# Adafruit_AR1100.net
KiCad netlist of a schematic drawn in EAGLE
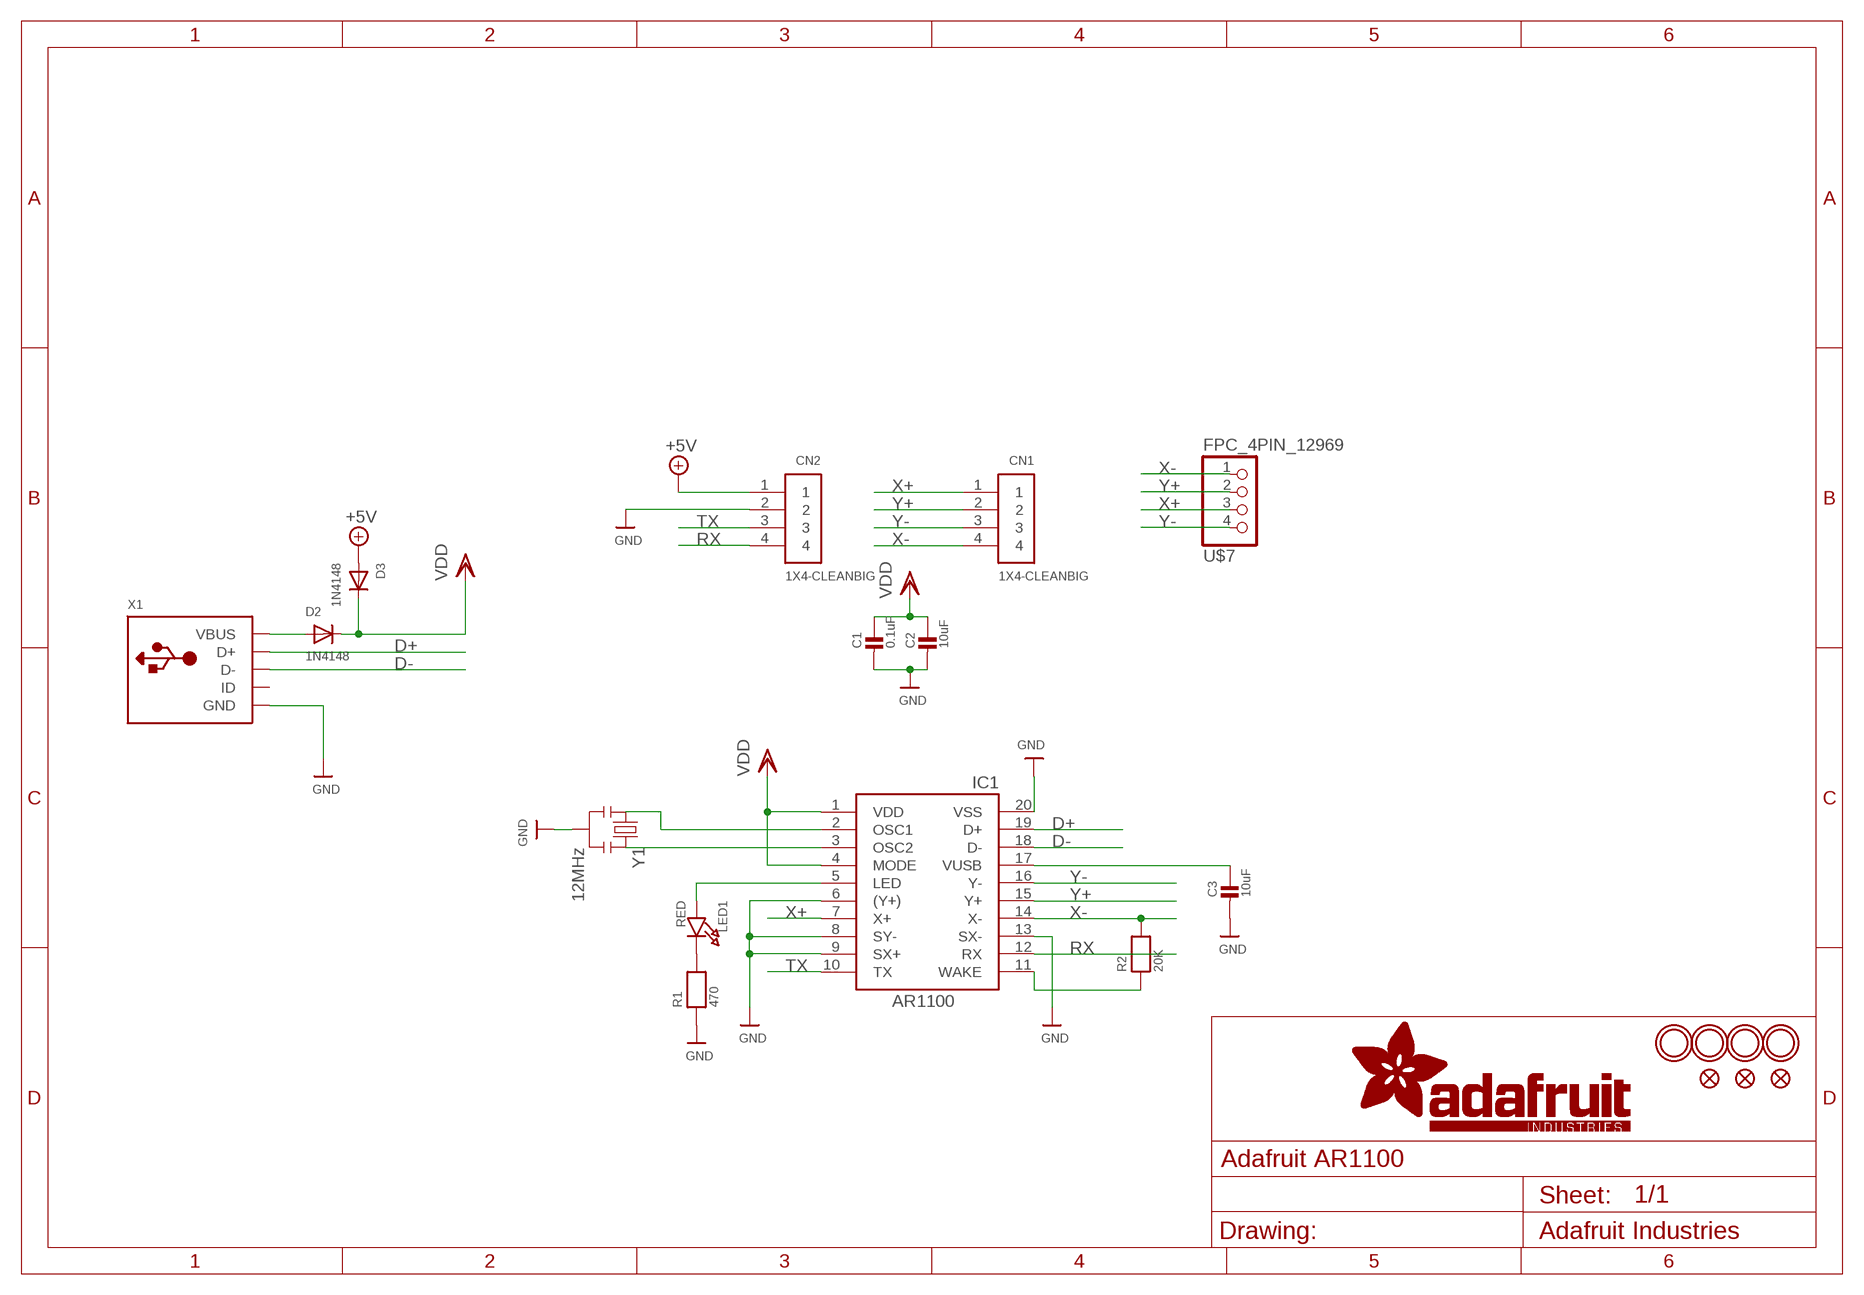
[diagram p0: schematic, sheet 1]

(export (version "E")
  (design (tool "Eeschema 10.0.6"))
  (components
    (comp (ref "C1")
      (value "0.1uF")
      (footprint "eagle-import:0805-NO")
      (libsource (lib "eagle-import") (part "CAP_CERAMIC0805-NOOUTLINE"))
    )
    (comp (ref "C2")
      (value "10uF")
      (footprint "eagle-import:0805-NO")
      (libsource (lib "eagle-import") (part "CAP_CERAMIC0805-NOOUTLINE"))
    )
    (comp (ref "C3")
      (value "10uF")
      (footprint "eagle-import:0805-NO")
      (libsource (lib "eagle-import") (part "CAP_CERAMIC0805-NOOUTLINE"))
    )
    (comp (ref "CN1")
      (value "1X4-CLEANBIG")
      (footprint "eagle-import:1X04-CLEANBIG")
      (libsource (lib "eagle-import") (part "1X4-CLEANBIG"))
    )
    (comp (ref "CN2")
      (value "1X4-CLEANBIG")
      (footprint "eagle-import:1X04-CLEANBIG")
      (libsource (lib "eagle-import") (part "1X4-CLEANBIG"))
    )
    (comp (ref "D2")
      (value "1N4148")
      (footprint "eagle-import:SOD-323F")
      (libsource (lib "eagle-import") (part "DIODESOD-323F"))
    )
    (comp (ref "D3")
      (value "1N4148")
      (footprint "eagle-import:SOD-323F")
      (libsource (lib "eagle-import") (part "DIODESOD-323F"))
    )
    (comp (ref "FID1")
      (value "FIDUCIAL\"\"")
      (footprint "eagle-import:FIDUCIAL_1MM")
      (libsource (lib "eagle-import") (part "FIDUCIAL{dblquote}{dblquote}"))
    )
    (comp (ref "FID2")
      (value "FIDUCIAL\"\"")
      (footprint "eagle-import:FIDUCIAL_1MM")
      (libsource (lib "eagle-import") (part "FIDUCIAL{dblquote}{dblquote}"))
    )
    (comp (ref "FID3")
      (value "FIDUCIAL\"\"")
      (footprint "eagle-import:FIDUCIAL_1MM")
      (fields (field (name "BOM") "EXCLUDE"))
      (libsource (lib "eagle-import") (part "FIDUCIAL{dblquote}{dblquote}"))
    )
    (comp (ref "IC1")
      (value "AR1100_SSOP")
      (footprint "eagle-import:TSSOP20-5.3MMBODY")
      (libsource (lib "eagle-import") (part "AR1100_SSOP"))
    )
    (comp (ref "LED1")
      (value "RED")
      (footprint "eagle-import:CHIPLED_0805_NOOUTLINE")
      (libsource (lib "eagle-import") (part "LED0805_NOOUTLINE"))
    )
    (comp (ref "R1")
      (value "470")
      (footprint "eagle-import:0805-NO")
      (libsource (lib "eagle-import") (part "RESISTOR0805_NOOUTLINE"))
    )
    (comp (ref "R2")
      (value "20K")
      (footprint "eagle-import:0805-NO")
      (libsource (lib "eagle-import") (part "RESISTOR0805_NOOUTLINE"))
    )
    (comp (ref "U$2")
      (value "MOUNTINGHOLE2.5")
      (footprint "eagle-import:MOUNTINGHOLE_2.5_PLATED")
      (fields (field (name "BOM") "EXCLUDE"))
      (libsource (lib "eagle-import") (part "MOUNTINGHOLE2.5"))
    )
    (comp (ref "U$4")
      (value "MOUNTINGHOLE2.5")
      (footprint "eagle-import:MOUNTINGHOLE_2.5_PLATED")
      (libsource (lib "eagle-import") (part "MOUNTINGHOLE2.5"))
    )
    (comp (ref "U$5")
      (value "MOUNTINGHOLE2.5")
      (footprint "eagle-import:MOUNTINGHOLE_2.5_PLATED")
      (libsource (lib "eagle-import") (part "MOUNTINGHOLE2.5"))
    )
    (comp (ref "U$6")
      (value "MOUNTINGHOLE2.5")
      (footprint "eagle-import:MOUNTINGHOLE_2.5_PLATED")
      (fields (field (name "BOM") "EXCLUDE"))
      (libsource (lib "eagle-import") (part "MOUNTINGHOLE2.5"))
    )
    (comp (ref "U$7")
      (value "FPC_4PIN_12969")
      (footprint "eagle-import:FPC_CONN_1MM_DUAL_4P")
      (libsource (lib "eagle-import") (part "FPC_4PIN_12969"))
    )
    (comp (ref "X1")
      (value "USBMINIB")
      (footprint "eagle-import:USB-MINIB")
      (libsource (lib "eagle-import") (part "USBMINIB"))
    )
    (comp (ref "Y1")
      (value "12MHz")
      (footprint "eagle-import:RESONATOR-SMD")
      (libsource (lib "eagle-import") (part "RESONATORSMD"))
    )
  )
  (nets
    (net (code "1") (name "+5V") (class "Default")
      (node (ref "CN2") (pin "1") (pinfunction "1_1") (pintype "bidirectional"))
      (node (ref "D3") (pin "A") (pinfunction "A_A") (pintype "passive"))
    )
    (net (code "2") (name "/D+") (class "Default")
      (node (ref "IC1") (pin "19") (pinfunction "D+_19") (pintype "bidirectional"))
      (node (ref "X1") (pin "D+") (pinfunction "D+_D+") (pintype "bidirectional"))
    )
    (net (code "3") (name "/D-") (class "Default")
      (node (ref "IC1") (pin "18") (pinfunction "D-_18") (pintype "bidirectional"))
      (node (ref "X1") (pin "D-") (pinfunction "D-_D-") (pintype "bidirectional"))
    )
    (net (code "4") (name "/RX") (class "Default")
      (node (ref "CN2") (pin "4") (pinfunction "4_4") (pintype "bidirectional"))
      (node (ref "IC1") (pin "12") (pinfunction "RX_12") (pintype "input"))
    )
    (net (code "5") (name "/TX") (class "Default")
      (node (ref "CN2") (pin "3") (pinfunction "3_3") (pintype "bidirectional"))
      (node (ref "IC1") (pin "10") (pinfunction "TX_10") (pintype "output"))
    )
    (net (code "6") (name "/X+") (class "Default")
      (node (ref "CN1") (pin "1") (pinfunction "1_1") (pintype "bidirectional"))
      (node (ref "IC1") (pin "7") (pinfunction "X+_7") (pintype "bidirectional"))
      (node (ref "U$7") (pin "3") (pinfunction "2_3") (pintype "passive"))
    )
    (net (code "7") (name "/X-") (class "Default")
      (node (ref "CN1") (pin "4") (pinfunction "4_4") (pintype "bidirectional"))
      (node (ref "IC1") (pin "14") (pinfunction "X-_14") (pintype "bidirectional"))
      (node (ref "R2") (pin "2") (pinfunction "2_2") (pintype "passive"))
      (node (ref "U$7") (pin "1") (pinfunction "4_1") (pintype "passive"))
    )
    (net (code "8") (name "/Y+") (class "Default")
      (node (ref "CN1") (pin "2") (pinfunction "2_2") (pintype "bidirectional"))
      (node (ref "IC1") (pin "15") (pinfunction "Y+_15") (pintype "bidirectional"))
      (node (ref "U$7") (pin "2") (pinfunction "3_2") (pintype "passive"))
    )
    (net (code "9") (name "/Y-") (class "Default")
      (node (ref "CN1") (pin "3") (pinfunction "3_3") (pintype "bidirectional"))
      (node (ref "IC1") (pin "16") (pinfunction "Y-_16") (pintype "bidirectional"))
      (node (ref "U$7") (pin "4") (pinfunction "1_4") (pintype "passive"))
    )
    (net (code "10") (name "GND") (class "Default")
      (node (ref "C1") (pin "2") (pinfunction "2_2") (pintype "passive"))
      (node (ref "C2") (pin "2") (pinfunction "2_2") (pintype "passive"))
      (node (ref "C3") (pin "2") (pinfunction "2_2") (pintype "passive"))
      (node (ref "CN2") (pin "2") (pinfunction "2_2") (pintype "bidirectional"))
      (node (ref "IC1") (pin "13") (pinfunction "SX-_13") (pintype "bidirectional"))
      (node (ref "IC1") (pin "20") (pinfunction "VSS_20") (pintype "power_in"))
      (node (ref "IC1") (pin "6") (pinfunction "(Y+)_6") (pintype "bidirectional"))
      (node (ref "IC1") (pin "8") (pinfunction "SY-_8") (pintype "bidirectional"))
      (node (ref "IC1") (pin "9") (pinfunction "SX+_9") (pintype "bidirectional"))
      (node (ref "R1") (pin "1") (pinfunction "1_1") (pintype "passive"))
      (node (ref "X1") (pin "GND") (pinfunction "GND_GND") (pintype "power_in"))
      (node (ref "X1") (pin "GND1") (pinfunction "GND_GND1") (pintype "power_in"))
      (node (ref "X1") (pin "GND2") (pinfunction "GND_GND2") (pintype "power_in"))
      (node (ref "X1") (pin "GND3") (pinfunction "GND_GND3") (pintype "power_in"))
      (node (ref "X1") (pin "GND4") (pinfunction "GND_GND4") (pintype "power_in"))
      (node (ref "Y1") (pin "2") (pinfunction "2_2") (pintype "passive"))
    )
    (net (code "11") (name "Net-(D2-PadA)") (class "Default")
      (node (ref "D2") (pin "A") (pinfunction "A_A") (pintype "passive"))
      (node (ref "X1") (pin "VBUS") (pinfunction "VBUS_VBUS") (pintype "power_in"))
    )
    (net (code "12") (name "Net-(IC1-LED)") (class "Default")
      (node (ref "IC1") (pin "5") (pinfunction "LED_5") (pintype "output"))
      (node (ref "LED1") (pin "A") (pinfunction "A_A") (pintype "passive"))
    )
    (net (code "13") (name "Net-(IC1-OSC1)") (class "Default")
      (node (ref "IC1") (pin "2") (pinfunction "OSC1_2") (pintype "passive"))
      (node (ref "Y1") (pin "1") (pinfunction "1_1") (pintype "passive"))
    )
    (net (code "14") (name "Net-(IC1-OSC2)") (class "Default")
      (node (ref "IC1") (pin "3") (pinfunction "OSC2_3") (pintype "passive"))
      (node (ref "Y1") (pin "3") (pinfunction "3_3") (pintype "passive"))
    )
    (net (code "15") (name "Net-(IC1-VUSB)") (class "Default")
      (node (ref "C3") (pin "1") (pinfunction "1_1") (pintype "passive"))
      (node (ref "IC1") (pin "17") (pinfunction "VUSB_17") (pintype "power_in"))
    )
    (net (code "16") (name "Net-(IC1-WAKE)") (class "Default")
      (node (ref "IC1") (pin "11") (pinfunction "WAKE_11") (pintype "input"))
      (node (ref "R2") (pin "1") (pinfunction "1_1") (pintype "passive"))
    )
    (net (code "17") (name "Net-(LED1-PadC)") (class "Default")
      (node (ref "LED1") (pin "C") (pinfunction "C_C") (pintype "passive"))
      (node (ref "R1") (pin "2") (pinfunction "2_2") (pintype "passive"))
    )
    (net (code "18") (name "VDD") (class "Default")
      (node (ref "C1") (pin "1") (pinfunction "1_1") (pintype "passive"))
      (node (ref "C2") (pin "1") (pinfunction "1_1") (pintype "passive"))
      (node (ref "D2") (pin "C") (pinfunction "C_C") (pintype "passive"))
      (node (ref "D3") (pin "C") (pinfunction "C_C") (pintype "passive"))
      (node (ref "IC1") (pin "1") (pinfunction "VDD_1") (pintype "power_in"))
      (node (ref "IC1") (pin "4") (pinfunction "MODE_4") (pintype "input"))
    )
    (net (code "19") (name "unconnected-(X1-PadID)") (class "Default")
      (node (ref "X1") (pin "ID") (pinfunction "ID_ID") (pintype "bidirectional"))
    )
  )
)
